# RGB_Taster_WS2811.net
KiCad netlist of a schematic drawn in EAGLE
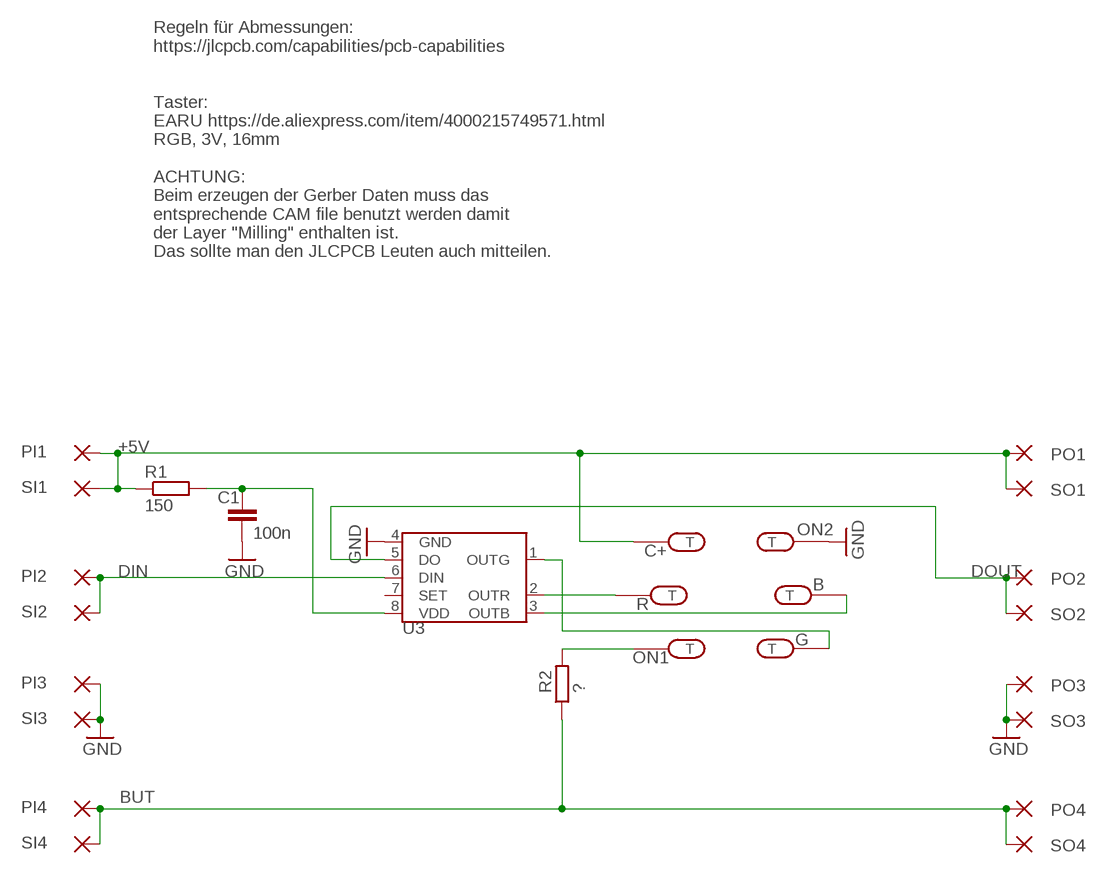
[diagram p0: schematic, sheet 1]

(export (version "E")
  (design (tool "Eeschema 10.0.6"))
  (components
    (comp (ref "B")
      (value "LANG_LOCH2")
      (footprint "eagle-import:LANG_LOCH2")
      (libsource (lib "eagle-import") (part "LANG_LOCH2"))
    )
    (comp (ref "C+")
      (value "LANG_LOCH2")
      (footprint "eagle-import:LANG_LOCH2")
      (libsource (lib "eagle-import") (part "LANG_LOCH2"))
    )
    (comp (ref "C1")
      (value "100n")
      (footprint "eagle-import:C0603")
      (libsource (lib "eagle-import") (part "C-EUC0603"))
    )
    (comp (ref "G")
      (value "LANG_LOCH2")
      (footprint "eagle-import:LANG_LOCH2")
      (libsource (lib "eagle-import") (part "LANG_LOCH2"))
    )
    (comp (ref "ON1")
      (value "LANG_LOCH2")
      (footprint "eagle-import:LANG_LOCH2")
      (libsource (lib "eagle-import") (part "LANG_LOCH2"))
    )
    (comp (ref "ON2")
      (value "LANG_LOCH2")
      (footprint "eagle-import:LANG_LOCH2")
      (libsource (lib "eagle-import") (part "LANG_LOCH2"))
    )
    (comp (ref "PI1")
      (value "SMD2")
      (footprint "eagle-import:SMD1,27-2,54")
      (libsource (lib "eagle-import") (part "SMD2"))
    )
    (comp (ref "PI2")
      (value "SMD2")
      (footprint "eagle-import:SMD1,27-2,54")
      (libsource (lib "eagle-import") (part "SMD2"))
    )
    (comp (ref "PI3")
      (value "SMD2")
      (footprint "eagle-import:SMD1,27-2,54")
      (libsource (lib "eagle-import") (part "SMD2"))
    )
    (comp (ref "PI4")
      (value "SMD2")
      (footprint "eagle-import:SMD1,27-2,54")
      (libsource (lib "eagle-import") (part "SMD2"))
    )
    (comp (ref "PO1")
      (value "SMD2")
      (footprint "eagle-import:SMD1,27-2,54")
      (libsource (lib "eagle-import") (part "SMD2"))
    )
    (comp (ref "PO2")
      (value "SMD2")
      (footprint "eagle-import:SMD1,27-2,54")
      (libsource (lib "eagle-import") (part "SMD2"))
    )
    (comp (ref "PO3")
      (value "SMD2")
      (footprint "eagle-import:SMD1,27-2,54")
      (libsource (lib "eagle-import") (part "SMD2"))
    )
    (comp (ref "PO4")
      (value "SMD2")
      (footprint "eagle-import:SMD1,27-2,54")
      (libsource (lib "eagle-import") (part "SMD2"))
    )
    (comp (ref "R")
      (value "LANG_LOCH2")
      (footprint "eagle-import:LANG_LOCH2")
      (libsource (lib "eagle-import") (part "LANG_LOCH2"))
    )
    (comp (ref "R1")
      (value "150")
      (footprint "eagle-import:RCL_R0603")
      (libsource (lib "eagle-import") (part "RCL_R-EU_R0603"))
    )
    (comp (ref "R2")
      (value "?")
      (footprint "eagle-import:RCL_R0603")
      (libsource (lib "eagle-import") (part "RCL_R-EU_R0603"))
    )
    (comp (ref "SI1")
      (value "SMD2")
      (footprint "eagle-import:SMD1,27-2,54")
      (libsource (lib "eagle-import") (part "SMD2"))
    )
    (comp (ref "SI2")
      (value "SMD2")
      (footprint "eagle-import:SMD1,27-2,54")
      (libsource (lib "eagle-import") (part "SMD2"))
    )
    (comp (ref "SI3")
      (value "SMD2")
      (footprint "eagle-import:SMD1,27-2,54")
      (libsource (lib "eagle-import") (part "SMD2"))
    )
    (comp (ref "SI4")
      (value "SMD2")
      (footprint "eagle-import:SMD1,27-2,54")
      (libsource (lib "eagle-import") (part "SMD2"))
    )
    (comp (ref "SO1")
      (value "SMD2")
      (footprint "eagle-import:SMD1,27-2,54")
      (libsource (lib "eagle-import") (part "SMD2"))
    )
    (comp (ref "SO2")
      (value "SMD2")
      (footprint "eagle-import:SMD1,27-2,54")
      (libsource (lib "eagle-import") (part "SMD2"))
    )
    (comp (ref "SO3")
      (value "SMD2")
      (footprint "eagle-import:SMD1,27-2,54")
      (libsource (lib "eagle-import") (part "SMD2"))
    )
    (comp (ref "SO4")
      (value "SMD2")
      (footprint "eagle-import:SMD1,27-2,54")
      (libsource (lib "eagle-import") (part "SMD2"))
    )
    (comp (ref "U3")
      (value "WS2811")
      (footprint "eagle-import:SOP8")
      (libsource (lib "eagle-import") (part "S3PO_MODUL_WS2811_SOUND_MP3-TF-16P_WS2811_AND_ATTINY_WS2811-ICSOP8"))
    )
  )
  (nets
    (net (code "1") (name "/+5V") (class "Default")
      (node (ref "C+") (pin "P$1") (pinfunction "T_P$1") (pintype "bidirectional"))
      (node (ref "C+") (pin "P$2") (pinfunction "T_P$2") (pintype "bidirectional"))
      (node (ref "PI1") (pin "1") (pinfunction "P_1") (pintype "passive"))
      (node (ref "PO1") (pin "1") (pinfunction "P_1") (pintype "passive"))
      (node (ref "R1") (pin "1") (pinfunction "1_1") (pintype "passive"))
      (node (ref "SI1") (pin "1") (pinfunction "P_1") (pintype "passive"))
      (node (ref "SO1") (pin "1") (pinfunction "P_1") (pintype "passive"))
    )
    (net (code "2") (name "/BUT") (class "Default")
      (node (ref "PI4") (pin "1") (pinfunction "P_1") (pintype "passive"))
      (node (ref "PO4") (pin "1") (pinfunction "P_1") (pintype "passive"))
      (node (ref "R2") (pin "1") (pinfunction "1_1") (pintype "passive"))
      (node (ref "SI4") (pin "1") (pinfunction "P_1") (pintype "passive"))
      (node (ref "SO4") (pin "1") (pinfunction "P_1") (pintype "passive"))
    )
    (net (code "3") (name "/DIN") (class "Default")
      (node (ref "PI2") (pin "1") (pinfunction "P_1") (pintype "passive"))
      (node (ref "SI2") (pin "1") (pinfunction "P_1") (pintype "passive"))
      (node (ref "U3") (pin "6") (pinfunction "DIN_6") (pintype "input"))
    )
    (net (code "4") (name "/DOUT") (class "Default")
      (node (ref "PO2") (pin "1") (pinfunction "P_1") (pintype "passive"))
      (node (ref "SO2") (pin "1") (pinfunction "P_1") (pintype "passive"))
      (node (ref "U3") (pin "5") (pinfunction "DO_5") (pintype "output"))
    )
    (net (code "5") (name "GND") (class "Default")
      (node (ref "C1") (pin "2") (pinfunction "2_2") (pintype "passive"))
      (node (ref "ON2") (pin "P$1") (pinfunction "T_P$1") (pintype "bidirectional"))
      (node (ref "ON2") (pin "P$2") (pinfunction "T_P$2") (pintype "bidirectional"))
      (node (ref "PI3") (pin "1") (pinfunction "P_1") (pintype "passive"))
      (node (ref "PO3") (pin "1") (pinfunction "P_1") (pintype "passive"))
      (node (ref "SI3") (pin "1") (pinfunction "P_1") (pintype "passive"))
      (node (ref "SO3") (pin "1") (pinfunction "P_1") (pintype "passive"))
      (node (ref "U3") (pin "4") (pinfunction "GND_4") (pintype "power_in"))
    )
    (net (code "6") (name "Net-(ON1-T-PadP$1)") (class "Default")
      (node (ref "ON1") (pin "P$1") (pinfunction "T_P$1") (pintype "bidirectional"))
      (node (ref "ON1") (pin "P$2") (pinfunction "T_P$2") (pintype "bidirectional"))
      (node (ref "R2") (pin "2") (pinfunction "2_2") (pintype "passive"))
    )
    (net (code "7") (name "Net-(U3-OUTB)") (class "Default")
      (node (ref "B") (pin "P$1") (pinfunction "T_P$1") (pintype "bidirectional"))
      (node (ref "B") (pin "P$2") (pinfunction "T_P$2") (pintype "bidirectional"))
      (node (ref "U3") (pin "3") (pinfunction "OUTB_3") (pintype "open_collector"))
    )
    (net (code "8") (name "Net-(U3-OUTG)") (class "Default")
      (node (ref "G") (pin "P$1") (pinfunction "T_P$1") (pintype "bidirectional"))
      (node (ref "G") (pin "P$2") (pinfunction "T_P$2") (pintype "bidirectional"))
      (node (ref "U3") (pin "1") (pinfunction "OUTG_1") (pintype "open_collector"))
    )
    (net (code "9") (name "Net-(U3-OUTR)") (class "Default")
      (node (ref "R") (pin "P$1") (pinfunction "T_P$1") (pintype "bidirectional"))
      (node (ref "R") (pin "P$2") (pinfunction "T_P$2") (pintype "bidirectional"))
      (node (ref "U3") (pin "2") (pinfunction "OUTR_2") (pintype "open_collector"))
    )
    (net (code "10") (name "Net-(U3-VDD)") (class "Default")
      (node (ref "C1") (pin "1") (pinfunction "1_1") (pintype "passive"))
      (node (ref "R1") (pin "2") (pinfunction "2_2") (pintype "passive"))
      (node (ref "U3") (pin "8") (pinfunction "VDD_8") (pintype "power_in"))
    )
    (net (code "11") (name "unconnected-(U3-SET-Pad7)") (class "Default")
      (node (ref "U3") (pin "7") (pinfunction "SET_7") (pintype "bidirectional"))
    )
  )
)
